# ARC_Doser.net
KiCad netlist of a schematic drawn in EAGLE
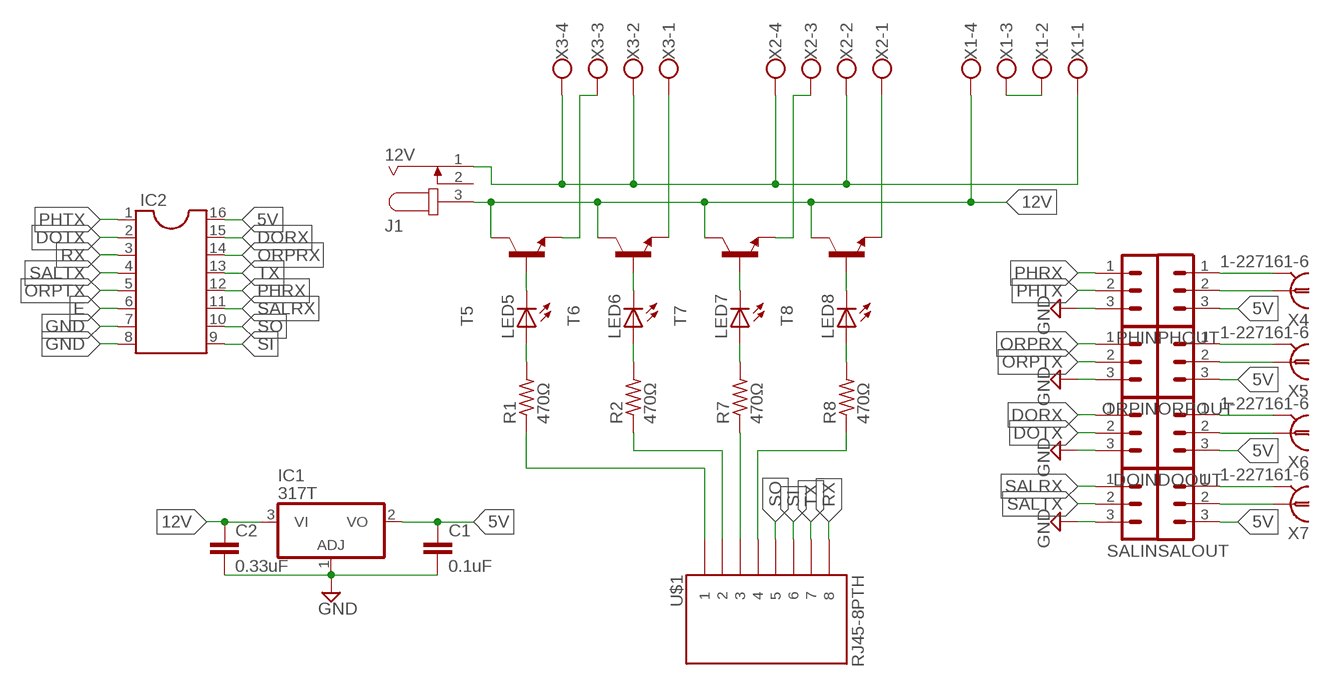
[diagram p0: schematic, sheet 1]

(export (version "E")
  (design (tool "Eeschema 10.0.6"))
  (components
    (comp (ref "C1")
      (value "0.1uF")
      (footprint "eagle-import:C5B3")
      (libsource (lib "eagle-import") (part "C5/3"))
    )
    (comp (ref "C2")
      (value "0.33uF")
      (footprint "eagle-import:C5B3")
      (libsource (lib "eagle-import") (part "C5/3"))
    )
    (comp (ref "DOIN")
      (value "MA03-1")
      (footprint "eagle-import:MA03-1")
      (libsource (lib "eagle-import") (part "MA03-1"))
    )
    (comp (ref "DOOUT")
      (value "MA03-1")
      (footprint "eagle-import:MA03-1")
      (libsource (lib "eagle-import") (part "MA03-1"))
    )
    (comp (ref "IC1")
      (value "317T")
      (footprint "eagle-import:TO220H")
      (libsource (lib "eagle-import") (part "317T"))
    )
    (comp (ref "IC2")
      (value "DIL16")
      (footprint "eagle-import:DIL16")
      (libsource (lib "eagle-import") (part "DIL16"))
    )
    (comp (ref "J1")
      (value "12V")
      (footprint "eagle-import:SPC4077")
      (libsource (lib "eagle-import") (part "JACK-PLUG0"))
    )
    (comp (ref "LED5")
      (value "LED3MM")
      (footprint "eagle-import:LED3MM")
      (libsource (lib "eagle-import") (part "LED3MM"))
    )
    (comp (ref "LED6")
      (value "LED3MM")
      (footprint "eagle-import:LED3MM")
      (libsource (lib "eagle-import") (part "LED3MM"))
    )
    (comp (ref "LED7")
      (value "LED3MM")
      (footprint "eagle-import:LED3MM")
      (libsource (lib "eagle-import") (part "LED3MM"))
    )
    (comp (ref "LED8")
      (value "LED3MM")
      (footprint "eagle-import:LED3MM")
      (libsource (lib "eagle-import") (part "LED3MM"))
    )
    (comp (ref "ORPIN")
      (value "MA03-1")
      (footprint "eagle-import:MA03-1")
      (libsource (lib "eagle-import") (part "MA03-1"))
    )
    (comp (ref "ORPOUT")
      (value "MA03-1")
      (footprint "eagle-import:MA03-1")
      (libsource (lib "eagle-import") (part "MA03-1"))
    )
    (comp (ref "PHIN")
      (value "MA03-1")
      (footprint "eagle-import:MA03-1")
      (libsource (lib "eagle-import") (part "MA03-1"))
    )
    (comp (ref "PHOUT")
      (value "MA03-1")
      (footprint "eagle-import:MA03-1")
      (libsource (lib "eagle-import") (part "MA03-1"))
    )
    (comp (ref "R1")
      (value "470Ω")
      (footprint "eagle-import:0204_7")
      (libsource (lib "eagle-import") (part "R-US_0204/7"))
    )
    (comp (ref "R2")
      (value "470Ω")
      (footprint "eagle-import:0204_7")
      (libsource (lib "eagle-import") (part "R-US_0204/7"))
    )
    (comp (ref "R7")
      (value "470Ω")
      (footprint "eagle-import:0204_7")
      (libsource (lib "eagle-import") (part "R-US_0204/7"))
    )
    (comp (ref "R8")
      (value "470Ω")
      (footprint "eagle-import:0204_7")
      (libsource (lib "eagle-import") (part "R-US_0204/7"))
    )
    (comp (ref "SALIN")
      (value "MA03-1")
      (footprint "eagle-import:MA03-1")
      (libsource (lib "eagle-import") (part "MA03-1"))
    )
    (comp (ref "SALOUT")
      (value "MA03-1")
      (footprint "eagle-import:MA03-1")
      (libsource (lib "eagle-import") (part "MA03-1"))
    )
    (comp (ref "T5")
      (value "-NPN-TO92")
      (footprint "eagle-import:TO92")
      (libsource (lib "eagle-import") (part "-NPN-TO92"))
    )
    (comp (ref "T6")
      (value "-NPN-TO92")
      (footprint "eagle-import:TO92")
      (libsource (lib "eagle-import") (part "-NPN-TO92"))
    )
    (comp (ref "T7")
      (value "-NPN-TO92")
      (footprint "eagle-import:TO92")
      (libsource (lib "eagle-import") (part "-NPN-TO92"))
    )
    (comp (ref "T8")
      (value "-NPN-TO92")
      (footprint "eagle-import:TO92")
      (libsource (lib "eagle-import") (part "-NPN-TO92"))
    )
    (comp (ref "U$1")
      (value "RJ45-8PTH")
      (footprint "eagle-import:RJ45-8")
      (libsource (lib "eagle-import") (part "RJ45-8PTH"))
    )
    (comp (ref "X1")
      (value "W237-4")
      (footprint "eagle-import:W237-4")
      (libsource (lib "eagle-import") (part "W237-4"))
    )
    (comp (ref "X2")
      (value "W237-4")
      (footprint "eagle-import:W237-4")
      (libsource (lib "eagle-import") (part "W237-4"))
    )
    (comp (ref "X3")
      (value "W237-4")
      (footprint "eagle-import:W237-4")
      (libsource (lib "eagle-import") (part "W237-4"))
    )
    (comp (ref "X4")
      (value "1-227161-6")
      (footprint "eagle-import:AMP_227161")
      (fields (field (name "MF") "TYCO ELECTRONICS"))
      (libsource (lib "eagle-import") (part "?2271611--6"))
    )
    (comp (ref "X5")
      (value "1-227161-6")
      (footprint "eagle-import:AMP_227161")
      (fields (field (name "MF") "TYCO ELECTRONICS"))
      (libsource (lib "eagle-import") (part "?2271611--6"))
    )
    (comp (ref "X6")
      (value "1-227161-6")
      (footprint "eagle-import:AMP_227161")
      (fields (field (name "MF") "TYCO ELECTRONICS"))
      (libsource (lib "eagle-import") (part "?2271611--6"))
    )
    (comp (ref "X7")
      (value "1-227161-6")
      (footprint "eagle-import:AMP_227161")
      (fields (field (name "MF") "TYCO ELECTRONICS"))
      (libsource (lib "eagle-import") (part "?2271611--6"))
    )
  )
  (nets
    (net (code "1") (name "5V") (class "Default")
      (node (ref "C1") (pin "1") (pinfunction "1_1") (pintype "passive"))
      (node (ref "DOOUT") (pin "3") (pinfunction "3_3") (pintype "passive"))
      (node (ref "IC1") (pin "2") (pinfunction "VO_2") (pintype "passive"))
      (node (ref "IC2") (pin "16") (pinfunction "16_16") (pintype "passive"))
      (node (ref "ORPOUT") (pin "3") (pinfunction "3_3") (pintype "passive"))
      (node (ref "PHOUT") (pin "3") (pinfunction "3_3") (pintype "passive"))
      (node (ref "SALOUT") (pin "3") (pinfunction "3_3") (pintype "passive"))
    )
    (net (code "2") (name "12V") (class "Default")
      (node (ref "C2") (pin "1") (pinfunction "1_1") (pintype "passive"))
      (node (ref "IC1") (pin "3") (pinfunction "VI_3") (pintype "input"))
      (node (ref "J1") (pin "3") (pinfunction "3_3") (pintype "passive"))
      (node (ref "T5") (pin "3") (pinfunction "C_3") (pintype "passive"))
      (node (ref "T6") (pin "3") (pinfunction "C_3") (pintype "passive"))
      (node (ref "T7") (pin "3") (pinfunction "C_3") (pintype "passive"))
      (node (ref "T8") (pin "3") (pinfunction "C_3") (pintype "passive"))
      (node (ref "X1") (pin "4") (pinfunction "KL_4") (pintype "passive"))
    )
    (net (code "3") (name "DORX") (class "Default")
      (node (ref "DOIN") (pin "1") (pinfunction "1_1") (pintype "passive"))
      (node (ref "IC2") (pin "15") (pinfunction "15_15") (pintype "passive"))
    )
    (net (code "4") (name "DOTX") (class "Default")
      (node (ref "DOIN") (pin "2") (pinfunction "2_2") (pintype "passive"))
      (node (ref "IC2") (pin "2") (pinfunction "2_2") (pintype "passive"))
    )
    (net (code "5") (name "E") (class "Default")
      (node (ref "IC2") (pin "6") (pinfunction "6_6") (pintype "passive"))
    )
    (net (code "6") (name "GND") (class "Default")
      (node (ref "C1") (pin "2") (pinfunction "2_2") (pintype "passive"))
      (node (ref "C2") (pin "2") (pinfunction "2_2") (pintype "passive"))
      (node (ref "DOIN") (pin "3") (pinfunction "3_3") (pintype "passive"))
      (node (ref "IC1") (pin "1") (pinfunction "ADJ_1") (pintype "input"))
      (node (ref "IC2") (pin "7") (pinfunction "7_7") (pintype "passive"))
      (node (ref "IC2") (pin "8") (pinfunction "8_8") (pintype "passive"))
      (node (ref "J1") (pin "1") (pinfunction "1_1") (pintype "passive"))
      (node (ref "ORPIN") (pin "3") (pinfunction "3_3") (pintype "passive"))
      (node (ref "PHIN") (pin "3") (pinfunction "3_3") (pintype "passive"))
      (node (ref "SALIN") (pin "3") (pinfunction "3_3") (pintype "passive"))
      (node (ref "X1") (pin "1") (pinfunction "KL_1") (pintype "passive"))
      (node (ref "X2") (pin "2") (pinfunction "KL_2") (pintype "passive"))
      (node (ref "X2") (pin "4") (pinfunction "KL_4") (pintype "passive"))
      (node (ref "X3") (pin "2") (pinfunction "KL_2") (pintype "passive"))
      (node (ref "X3") (pin "4") (pinfunction "KL_4") (pintype "passive"))
    )
    (net (code "7") (name "Net-(DOOUT-Pad1)") (class "Default")
      (node (ref "DOOUT") (pin "1") (pinfunction "1_1") (pintype "passive"))
      (node (ref "X6") (pin "2") (pinfunction "2_2") (pintype "passive"))
    )
    (net (code "8") (name "Net-(DOOUT-Pad2)") (class "Default")
      (node (ref "DOOUT") (pin "2") (pinfunction "2_2") (pintype "passive"))
      (node (ref "X6") (pin "1") (pinfunction "1_1") (pintype "passive"))
    )
    (net (code "9") (name "Net-(LED5-C)") (class "Default")
      (node (ref "LED5") (pin "K") (pinfunction "C_K") (pintype "passive"))
      (node (ref "T5") (pin "2") (pinfunction "B_2") (pintype "passive"))
    )
    (net (code "10") (name "Net-(LED5-PadA)") (class "Default")
      (node (ref "LED5") (pin "A") (pinfunction "A_A") (pintype "passive"))
      (node (ref "R1") (pin "2") (pinfunction "2_2") (pintype "passive"))
    )
    (net (code "11") (name "Net-(LED6-C)") (class "Default")
      (node (ref "LED6") (pin "K") (pinfunction "C_K") (pintype "passive"))
      (node (ref "T6") (pin "2") (pinfunction "B_2") (pintype "passive"))
    )
    (net (code "12") (name "Net-(LED6-PadA)") (class "Default")
      (node (ref "LED6") (pin "A") (pinfunction "A_A") (pintype "passive"))
      (node (ref "R2") (pin "2") (pinfunction "2_2") (pintype "passive"))
    )
    (net (code "13") (name "Net-(LED7-C)") (class "Default")
      (node (ref "LED7") (pin "K") (pinfunction "C_K") (pintype "passive"))
      (node (ref "T7") (pin "2") (pinfunction "B_2") (pintype "passive"))
    )
    (net (code "14") (name "Net-(LED7-PadA)") (class "Default")
      (node (ref "LED7") (pin "A") (pinfunction "A_A") (pintype "passive"))
      (node (ref "R7") (pin "2") (pinfunction "2_2") (pintype "passive"))
    )
    (net (code "15") (name "Net-(LED8-C)") (class "Default")
      (node (ref "LED8") (pin "K") (pinfunction "C_K") (pintype "passive"))
      (node (ref "T8") (pin "2") (pinfunction "B_2") (pintype "passive"))
    )
    (net (code "16") (name "Net-(LED8-PadA)") (class "Default")
      (node (ref "LED8") (pin "A") (pinfunction "A_A") (pintype "passive"))
      (node (ref "R8") (pin "2") (pinfunction "2_2") (pintype "passive"))
    )
    (net (code "17") (name "Net-(ORPOUT-Pad1)") (class "Default")
      (node (ref "ORPOUT") (pin "1") (pinfunction "1_1") (pintype "passive"))
      (node (ref "X5") (pin "2") (pinfunction "2_2") (pintype "passive"))
    )
    (net (code "18") (name "Net-(ORPOUT-Pad2)") (class "Default")
      (node (ref "ORPOUT") (pin "2") (pinfunction "2_2") (pintype "passive"))
      (node (ref "X5") (pin "1") (pinfunction "1_1") (pintype "passive"))
    )
    (net (code "19") (name "Net-(PHOUT-Pad1)") (class "Default")
      (node (ref "PHOUT") (pin "1") (pinfunction "1_1") (pintype "passive"))
      (node (ref "X4") (pin "2") (pinfunction "2_2") (pintype "passive"))
    )
    (net (code "20") (name "Net-(PHOUT-Pad2)") (class "Default")
      (node (ref "PHOUT") (pin "2") (pinfunction "2_2") (pintype "passive"))
      (node (ref "X4") (pin "1") (pinfunction "1_1") (pintype "passive"))
    )
    (net (code "21") (name "Net-(R1-Pad1)") (class "Default")
      (node (ref "R1") (pin "1") (pinfunction "1_1") (pintype "passive"))
      (node (ref "U$1") (pin "1") (pinfunction "1_1") (pintype "bidirectional"))
    )
    (net (code "22") (name "Net-(R2-Pad1)") (class "Default")
      (node (ref "R2") (pin "1") (pinfunction "1_1") (pintype "passive"))
      (node (ref "U$1") (pin "2") (pinfunction "2_2") (pintype "bidirectional"))
    )
    (net (code "23") (name "Net-(R7-Pad1)") (class "Default")
      (node (ref "R7") (pin "1") (pinfunction "1_1") (pintype "passive"))
      (node (ref "U$1") (pin "3") (pinfunction "3_3") (pintype "bidirectional"))
    )
    (net (code "24") (name "Net-(R8-Pad1)") (class "Default")
      (node (ref "R8") (pin "1") (pinfunction "1_1") (pintype "passive"))
      (node (ref "U$1") (pin "4") (pinfunction "4_4") (pintype "bidirectional"))
    )
    (net (code "25") (name "Net-(SALOUT-Pad1)") (class "Default")
      (node (ref "SALOUT") (pin "1") (pinfunction "1_1") (pintype "passive"))
      (node (ref "X7") (pin "2") (pinfunction "2_2") (pintype "passive"))
    )
    (net (code "26") (name "Net-(SALOUT-Pad2)") (class "Default")
      (node (ref "SALOUT") (pin "2") (pinfunction "2_2") (pintype "passive"))
      (node (ref "X7") (pin "1") (pinfunction "1_1") (pintype "passive"))
    )
    (net (code "27") (name "Net-(T5-E)") (class "Default")
      (node (ref "T5") (pin "1") (pinfunction "E_1") (pintype "passive"))
      (node (ref "X3") (pin "3") (pinfunction "KL_3") (pintype "passive"))
    )
    (net (code "28") (name "Net-(T6-E)") (class "Default")
      (node (ref "T6") (pin "1") (pinfunction "E_1") (pintype "passive"))
      (node (ref "X3") (pin "1") (pinfunction "KL_1") (pintype "passive"))
    )
    (net (code "29") (name "Net-(T7-E)") (class "Default")
      (node (ref "T7") (pin "1") (pinfunction "E_1") (pintype "passive"))
      (node (ref "X2") (pin "3") (pinfunction "KL_3") (pintype "passive"))
    )
    (net (code "30") (name "Net-(T8-E)") (class "Default")
      (node (ref "T8") (pin "1") (pinfunction "E_1") (pintype "passive"))
      (node (ref "X2") (pin "1") (pinfunction "KL_1") (pintype "passive"))
    )
    (net (code "31") (name "Net-(X1B-KL)") (class "Default")
      (node (ref "X1") (pin "2") (pinfunction "KL_2") (pintype "passive"))
      (node (ref "X1") (pin "3") (pinfunction "KL_3") (pintype "passive"))
    )
    (net (code "32") (name "ORPRX") (class "Default")
      (node (ref "IC2") (pin "14") (pinfunction "14_14") (pintype "passive"))
      (node (ref "ORPIN") (pin "1") (pinfunction "1_1") (pintype "passive"))
    )
    (net (code "33") (name "ORPTX") (class "Default")
      (node (ref "IC2") (pin "5") (pinfunction "5_5") (pintype "passive"))
      (node (ref "ORPIN") (pin "2") (pinfunction "2_2") (pintype "passive"))
    )
    (net (code "34") (name "PHRX") (class "Default")
      (node (ref "IC2") (pin "12") (pinfunction "12_12") (pintype "passive"))
      (node (ref "PHIN") (pin "1") (pinfunction "1_1") (pintype "passive"))
    )
    (net (code "35") (name "PHTX") (class "Default")
      (node (ref "IC2") (pin "1") (pinfunction "1_1") (pintype "passive"))
      (node (ref "PHIN") (pin "2") (pinfunction "2_2") (pintype "passive"))
    )
    (net (code "36") (name "RX") (class "Default")
      (node (ref "IC2") (pin "3") (pinfunction "3_3") (pintype "passive"))
      (node (ref "U$1") (pin "8") (pinfunction "8_8") (pintype "bidirectional"))
    )
    (net (code "37") (name "SALRX") (class "Default")
      (node (ref "IC2") (pin "11") (pinfunction "11_11") (pintype "passive"))
      (node (ref "SALIN") (pin "1") (pinfunction "1_1") (pintype "passive"))
    )
    (net (code "38") (name "SALTX") (class "Default")
      (node (ref "IC2") (pin "4") (pinfunction "4_4") (pintype "passive"))
      (node (ref "SALIN") (pin "2") (pinfunction "2_2") (pintype "passive"))
    )
    (net (code "39") (name "SI") (class "Default")
      (node (ref "IC2") (pin "9") (pinfunction "9_9") (pintype "passive"))
      (node (ref "U$1") (pin "6") (pinfunction "6_6") (pintype "bidirectional"))
    )
    (net (code "40") (name "SO") (class "Default")
      (node (ref "IC2") (pin "10") (pinfunction "10_10") (pintype "passive"))
      (node (ref "U$1") (pin "5") (pinfunction "5_5") (pintype "bidirectional"))
    )
    (net (code "41") (name "TX") (class "Default")
      (node (ref "IC2") (pin "13") (pinfunction "13_13") (pintype "passive"))
      (node (ref "U$1") (pin "7") (pinfunction "7_7") (pintype "bidirectional"))
    )
    (net (code "42") (name "unconnected-(J1-Pad2)") (class "Default")
      (node (ref "J1") (pin "2") (pinfunction "2_2") (pintype "passive"))
    )
  )
)
